# ftdiemu.net
KiCad netlist of a schematic drawn in EAGLE
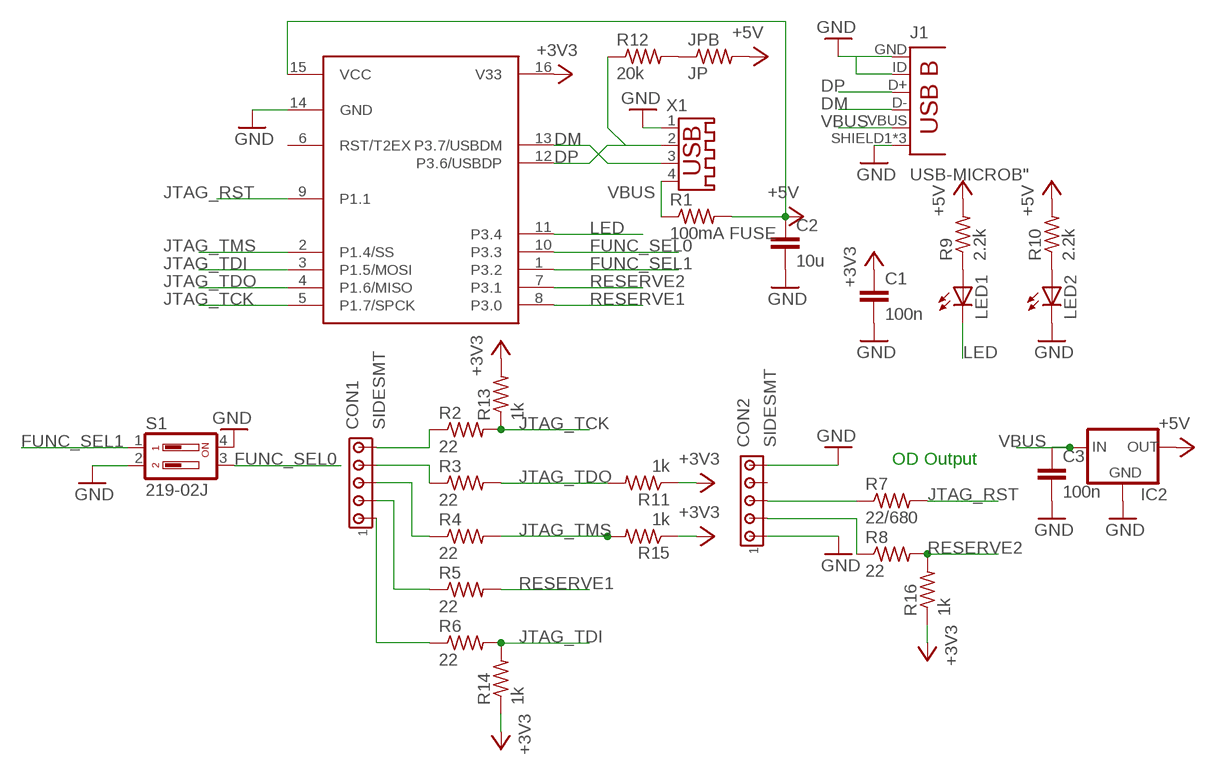
[diagram p0: schematic, sheet 1]

(export (version "E")
  (design (tool "Eeschema 10.0.6"))
  (components
    (comp (ref "C1")
      (value "100n")
      (footprint "eagle-import:C0805")
      (libsource (lib "eagle-import") (part "C-EUC0805"))
    )
    (comp (ref "C2")
      (value "10u")
      (footprint "eagle-import:C0805")
      (libsource (lib "eagle-import") (part "C-EUC0805"))
    )
    (comp (ref "C3")
      (value "100n")
      (footprint "eagle-import:C0805")
      (libsource (lib "eagle-import") (part "C-EUC0805"))
    )
    (comp (ref "CON1")
      (value "SIDESMT")
      (footprint "eagle-import:SIDESMT")
      (libsource (lib "eagle-import") (part "SIDESMT"))
    )
    (comp (ref "CON2")
      (value "SIDESMT")
      (footprint "eagle-import:SIDESMT")
      (libsource (lib "eagle-import") (part "SIDESMT"))
    )
    (comp (ref "IC1")
      (value "CH551G-16L")
      (footprint "eagle-import:SO-16")
      (libsource (lib "eagle-import") (part "CH551G-16L"))
    )
    (comp (ref "IC2")
      (value "XC63FPM")
      (footprint "eagle-import:SOT23")
      (libsource (lib "eagle-import") (part "XC63FPM"))
    )
    (comp (ref "J1")
      (value "USB-MICROB\"")
      (footprint "eagle-import:USB-B-MICRO-SMD_V03")
      (libsource (lib "eagle-import") (part "USB-MICROB{dblquote}"))
    )
    (comp (ref "JPB")
      (value "JP")
      (footprint "eagle-import:R0201")
      (libsource (lib "eagle-import") (part "R-US_R0201"))
    )
    (comp (ref "LED1")
      (value "LEDSML0805")
      (footprint "eagle-import:SML0805")
      (libsource (lib "eagle-import") (part "LEDSML0805"))
    )
    (comp (ref "LED2")
      (value "LEDSML0805")
      (footprint "eagle-import:SML0805")
      (libsource (lib "eagle-import") (part "LEDSML0805"))
    )
    (comp (ref "R1")
      (value "100mA FUSE")
      (footprint "eagle-import:M0805")
      (libsource (lib "eagle-import") (part "R-US_M0805"))
    )
    (comp (ref "R2")
      (value "22")
      (footprint "eagle-import:R0402")
      (libsource (lib "eagle-import") (part "R-US_R0402"))
    )
    (comp (ref "R3")
      (value "22")
      (footprint "eagle-import:R0402")
      (libsource (lib "eagle-import") (part "R-US_R0402"))
    )
    (comp (ref "R4")
      (value "22")
      (footprint "eagle-import:R0402")
      (libsource (lib "eagle-import") (part "R-US_R0402"))
    )
    (comp (ref "R5")
      (value "22")
      (footprint "eagle-import:R0402")
      (libsource (lib "eagle-import") (part "R-US_R0402"))
    )
    (comp (ref "R6")
      (value "22")
      (footprint "eagle-import:R0402")
      (libsource (lib "eagle-import") (part "R-US_R0402"))
    )
    (comp (ref "R7")
      (value "22/680")
      (footprint "eagle-import:R0402")
      (libsource (lib "eagle-import") (part "R-US_R0402"))
    )
    (comp (ref "R8")
      (value "22")
      (footprint "eagle-import:R0402")
      (libsource (lib "eagle-import") (part "R-US_R0402"))
    )
    (comp (ref "R9")
      (value "2.2k")
      (footprint "eagle-import:M0805")
      (libsource (lib "eagle-import") (part "R-US_M0805"))
    )
    (comp (ref "R10")
      (value "2.2k")
      (footprint "eagle-import:M0805")
      (libsource (lib "eagle-import") (part "R-US_M0805"))
    )
    (comp (ref "R11")
      (value "1k")
      (footprint "eagle-import:R0402")
      (libsource (lib "eagle-import") (part "R-US_R0402"))
    )
    (comp (ref "R12")
      (value "20k")
      (footprint "eagle-import:R0805")
      (libsource (lib "eagle-import") (part "R-US_R0805"))
    )
    (comp (ref "R13")
      (value "1k")
      (footprint "eagle-import:R0402")
      (libsource (lib "eagle-import") (part "R-US_R0402"))
    )
    (comp (ref "R14")
      (value "1k")
      (footprint "eagle-import:R0402")
      (libsource (lib "eagle-import") (part "R-US_R0402"))
    )
    (comp (ref "R15")
      (value "1k")
      (footprint "eagle-import:R0402")
      (libsource (lib "eagle-import") (part "R-US_R0402"))
    )
    (comp (ref "R16")
      (value "1k")
      (footprint "eagle-import:R0402")
      (libsource (lib "eagle-import") (part "R-US_R0402"))
    )
    (comp (ref "S1")
      (value "219-02J")
      (footprint "eagle-import:CTS-219-02J")
      (libsource (lib "eagle-import") (part "219-02J"))
    )
    (comp (ref "X1")
      (value "USB-A003")
      (footprint "eagle-import:USB-A003")
      (libsource (lib "eagle-import") (part "USB-A003"))
    )
  )
  (nets
    (net (code "1") (name "+3V3") (class "Default")
      (node (ref "C1") (pin "1") (pinfunction "1_1") (pintype "passive"))
      (node (ref "IC1") (pin "16") (pinfunction "V33_16") (pintype "bidirectional"))
      (node (ref "R11") (pin "1") (pinfunction "1_1") (pintype "passive"))
      (node (ref "R13") (pin "2") (pinfunction "2_2") (pintype "passive"))
      (node (ref "R14") (pin "1") (pinfunction "1_1") (pintype "passive"))
      (node (ref "R15") (pin "1") (pinfunction "1_1") (pintype "passive"))
      (node (ref "R16") (pin "1") (pinfunction "1_1") (pintype "passive"))
    )
    (net (code "2") (name "+5V") (class "Default")
      (node (ref "C2") (pin "1") (pinfunction "1_1") (pintype "passive"))
      (node (ref "IC1") (pin "15") (pinfunction "VCC_15") (pintype "bidirectional"))
      (node (ref "IC2") (pin "2") (pinfunction "OUT_2") (pintype "passive"))
      (node (ref "JPB") (pin "2") (pinfunction "2_2") (pintype "passive"))
      (node (ref "R1") (pin "2") (pinfunction "2_2") (pintype "passive"))
      (node (ref "R10") (pin "2") (pinfunction "2_2") (pintype "passive"))
      (node (ref "R9") (pin "2") (pinfunction "2_2") (pintype "passive"))
    )
    (net (code "3") (name "/DM") (class "Default")
      (node (ref "IC1") (pin "13") (pinfunction "P3.7/USBDM_13") (pintype "bidirectional"))
      (node (ref "J1") (pin "D-") (pinfunction "D-_D-") (pintype "bidirectional"))
      (node (ref "X1") (pin "3") (pinfunction "3_3") (pintype "passive"))
    )
    (net (code "4") (name "/DP") (class "Default")
      (node (ref "IC1") (pin "12") (pinfunction "P3.6/USBDP_12") (pintype "bidirectional"))
      (node (ref "J1") (pin "D+") (pinfunction "D+_D+") (pintype "bidirectional"))
      (node (ref "R12") (pin "1") (pinfunction "1_1") (pintype "passive"))
      (node (ref "X1") (pin "2") (pinfunction "2_2") (pintype "passive"))
    )
    (net (code "5") (name "/FUNC_SEL0") (class "Default")
      (node (ref "IC1") (pin "10") (pinfunction "P3.3_10") (pintype "bidirectional"))
      (node (ref "S1") (pin "3") (pinfunction "3_3") (pintype "passive"))
    )
    (net (code "6") (name "/FUNC_SEL1") (class "Default")
      (node (ref "IC1") (pin "1") (pinfunction "P3.2_1") (pintype "bidirectional"))
      (node (ref "S1") (pin "1") (pinfunction "1_1") (pintype "passive"))
    )
    (net (code "7") (name "/JTAG_RST") (class "Default")
      (node (ref "IC1") (pin "9") (pinfunction "P1.1_9") (pintype "bidirectional"))
      (node (ref "R7") (pin "2") (pinfunction "2_2") (pintype "passive"))
    )
    (net (code "8") (name "/JTAG_TCK") (class "Default")
      (node (ref "IC1") (pin "5") (pinfunction "P1.7/SPCK_5") (pintype "bidirectional"))
      (node (ref "R13") (pin "1") (pinfunction "1_1") (pintype "passive"))
      (node (ref "R2") (pin "2") (pinfunction "2_2") (pintype "passive"))
    )
    (net (code "9") (name "/JTAG_TDI") (class "Default")
      (node (ref "IC1") (pin "3") (pinfunction "P1.5/MOSI_3") (pintype "bidirectional"))
      (node (ref "R14") (pin "2") (pinfunction "2_2") (pintype "passive"))
      (node (ref "R6") (pin "2") (pinfunction "2_2") (pintype "passive"))
    )
    (net (code "10") (name "/JTAG_TDO") (class "Default")
      (node (ref "IC1") (pin "4") (pinfunction "P1.6/MISO_4") (pintype "bidirectional"))
      (node (ref "R11") (pin "2") (pinfunction "2_2") (pintype "passive"))
      (node (ref "R3") (pin "2") (pinfunction "2_2") (pintype "passive"))
    )
    (net (code "11") (name "/JTAG_TMS") (class "Default")
      (node (ref "IC1") (pin "2") (pinfunction "P1.4/SS_2") (pintype "bidirectional"))
      (node (ref "R15") (pin "2") (pinfunction "2_2") (pintype "passive"))
      (node (ref "R4") (pin "2") (pinfunction "2_2") (pintype "passive"))
    )
    (net (code "12") (name "/LED") (class "Default")
      (node (ref "IC1") (pin "11") (pinfunction "P3.4_11") (pintype "bidirectional"))
      (node (ref "LED1") (pin "C") (pinfunction "C_C") (pintype "passive"))
    )
    (net (code "13") (name "/RESERVE1") (class "Default")
      (node (ref "IC1") (pin "8") (pinfunction "P3.0_8") (pintype "bidirectional"))
      (node (ref "R5") (pin "2") (pinfunction "2_2") (pintype "passive"))
    )
    (net (code "14") (name "/RESERVE2") (class "Default")
      (node (ref "IC1") (pin "7") (pinfunction "P3.1_7") (pintype "bidirectional"))
      (node (ref "R16") (pin "2") (pinfunction "2_2") (pintype "passive"))
      (node (ref "R8") (pin "2") (pinfunction "2_2") (pintype "passive"))
    )
    (net (code "15") (name "/VBUS") (class "Default")
      (node (ref "C3") (pin "1") (pinfunction "1_1") (pintype "passive"))
      (node (ref "IC2") (pin "3") (pinfunction "IN_3") (pintype "input"))
      (node (ref "J1") (pin "VBUS") (pinfunction "VBUS_VBUS") (pintype "bidirectional"))
      (node (ref "R1") (pin "1") (pinfunction "1_1") (pintype "passive"))
      (node (ref "X1") (pin "4") (pinfunction "4_4") (pintype "passive"))
    )
    (net (code "16") (name "GND") (class "Default")
      (node (ref "C1") (pin "2") (pinfunction "2_2") (pintype "passive"))
      (node (ref "C2") (pin "2") (pinfunction "2_2") (pintype "passive"))
      (node (ref "C3") (pin "2") (pinfunction "2_2") (pintype "passive"))
      (node (ref "CON2") (pin "1") (pinfunction "1_1") (pintype "passive"))
      (node (ref "CON2") (pin "5") (pinfunction "5_5") (pintype "passive"))
      (node (ref "IC1") (pin "14") (pinfunction "GND_14") (pintype "bidirectional"))
      (node (ref "IC2") (pin "1") (pinfunction "GND_1") (pintype "input"))
      (node (ref "J1") (pin "GND") (pinfunction "GND_GND") (pintype "bidirectional"))
      (node (ref "J1") (pin "ID") (pinfunction "USBID_ID") (pintype "bidirectional"))
      (node (ref "J1") (pin "SHIELD1") (pinfunction "SHIELD_SHIELD1") (pintype "bidirectional"))
      (node (ref "J1") (pin "SHIELD2") (pinfunction "SHIELD_SHIELD2") (pintype "bidirectional"))
      (node (ref "J1") (pin "SHIELD3") (pinfunction "SHIELD_SHIELD3") (pintype "bidirectional"))
      (node (ref "LED2") (pin "C") (pinfunction "C_C") (pintype "passive"))
      (node (ref "S1") (pin "2") (pinfunction "2_2") (pintype "passive"))
      (node (ref "S1") (pin "4") (pinfunction "4_4") (pintype "passive"))
      (node (ref "X1") (pin "1") (pinfunction "1_1") (pintype "passive"))
    )
    (net (code "17") (name "Net-(CON1-Pad1)") (class "Default")
      (node (ref "CON1") (pin "1") (pinfunction "1_1") (pintype "passive"))
      (node (ref "R6") (pin "1") (pinfunction "1_1") (pintype "passive"))
    )
    (net (code "18") (name "Net-(CON1-Pad2)") (class "Default")
      (node (ref "CON1") (pin "2") (pinfunction "2_2") (pintype "passive"))
      (node (ref "R5") (pin "1") (pinfunction "1_1") (pintype "passive"))
    )
    (net (code "19") (name "Net-(CON1-Pad3)") (class "Default")
      (node (ref "CON1") (pin "3") (pinfunction "3_3") (pintype "passive"))
      (node (ref "R4") (pin "1") (pinfunction "1_1") (pintype "passive"))
    )
    (net (code "20") (name "Net-(CON1-Pad4)") (class "Default")
      (node (ref "CON1") (pin "4") (pinfunction "4_4") (pintype "passive"))
      (node (ref "R3") (pin "1") (pinfunction "1_1") (pintype "passive"))
    )
    (net (code "21") (name "Net-(CON1-Pad5)") (class "Default")
      (node (ref "CON1") (pin "5") (pinfunction "5_5") (pintype "passive"))
      (node (ref "R2") (pin "1") (pinfunction "1_1") (pintype "passive"))
    )
    (net (code "22") (name "Net-(CON2-Pad2)") (class "Default")
      (node (ref "CON2") (pin "2") (pinfunction "2_2") (pintype "passive"))
      (node (ref "R8") (pin "1") (pinfunction "1_1") (pintype "passive"))
    )
    (net (code "23") (name "Net-(CON2-Pad3)") (class "Default")
      (node (ref "CON2") (pin "3") (pinfunction "3_3") (pintype "passive"))
      (node (ref "R7") (pin "1") (pinfunction "1_1") (pintype "passive"))
    )
    (net (code "24") (name "Net-(JPB-Pad1)") (class "Default")
      (node (ref "JPB") (pin "1") (pinfunction "1_1") (pintype "passive"))
      (node (ref "R12") (pin "2") (pinfunction "2_2") (pintype "passive"))
    )
    (net (code "25") (name "Net-(LED1-PadA)") (class "Default")
      (node (ref "LED1") (pin "A") (pinfunction "A_A") (pintype "passive"))
      (node (ref "R9") (pin "1") (pinfunction "1_1") (pintype "passive"))
    )
    (net (code "26") (name "Net-(LED2-PadA)") (class "Default")
      (node (ref "LED2") (pin "A") (pinfunction "A_A") (pintype "passive"))
      (node (ref "R10") (pin "1") (pinfunction "1_1") (pintype "passive"))
    )
    (net (code "27") (name "unconnected-(CON2-Pad4)") (class "Default")
      (node (ref "CON2") (pin "4") (pinfunction "4_4") (pintype "passive"))
    )
    (net (code "28") (name "unconnected-(IC1-RST{slash}T2EX-Pad6)") (class "Default")
      (node (ref "IC1") (pin "6") (pinfunction "RST/T2EX_6") (pintype "bidirectional"))
    )
  )
)
